# Fabrickit-Bare-Brick.net
KiCad netlist of a schematic drawn in EAGLE
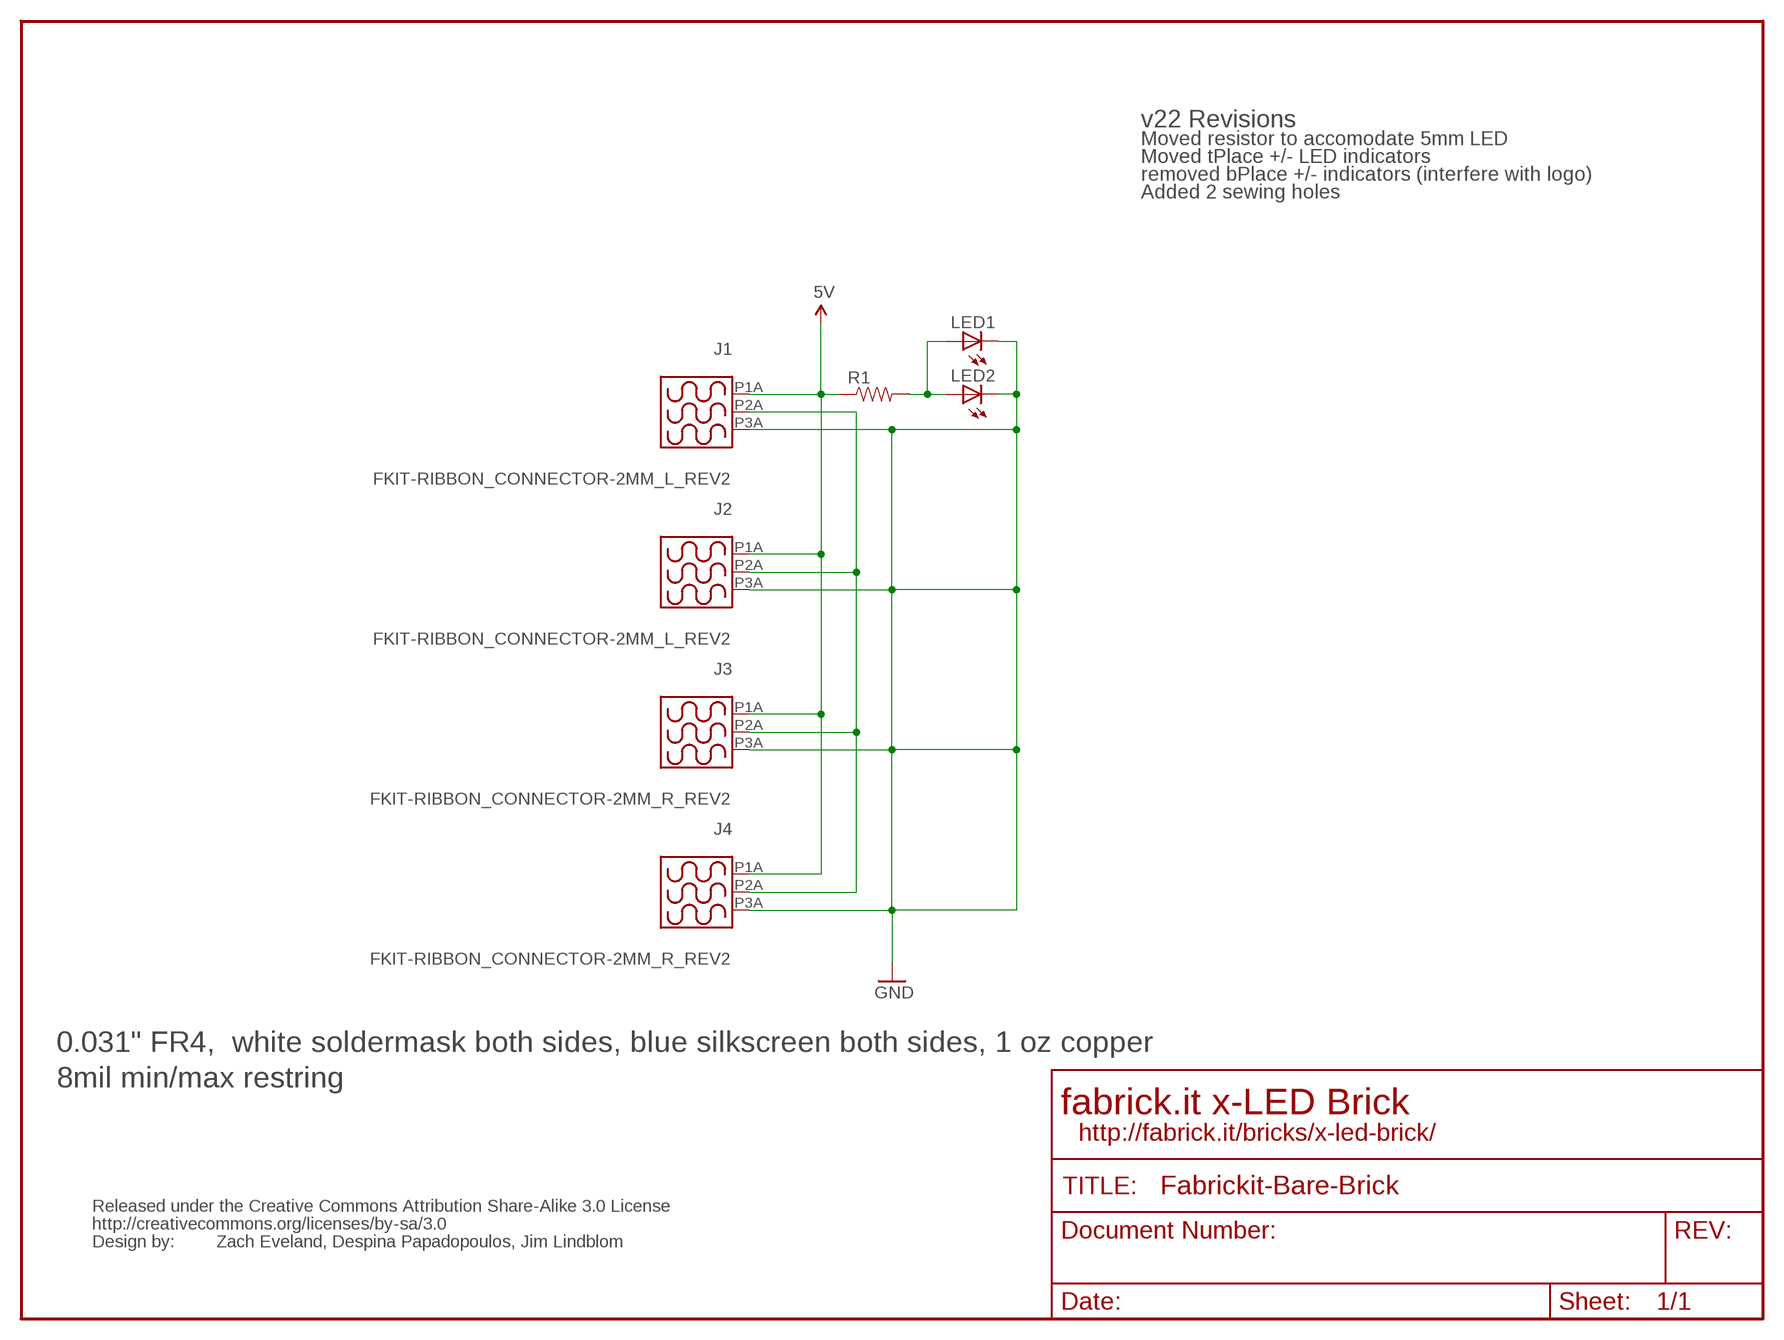
[diagram p0: schematic, sheet 1]

(export (version "E")
  (design (tool "Eeschema 10.0.6"))
  (components
    (comp (ref "J1")
      (value "FKIT-RIBBON_CONNECTOR-2MM_L_REV2")
      (footprint "eagle-import:FKIT-RIBBON_CONNECTOR_03_2MM_L")
      (libsource (lib "eagle-import") (part "FKIT-RIBBON_CONNECTOR-2MM_L_REV2"))
    )
    (comp (ref "J2")
      (value "FKIT-RIBBON_CONNECTOR-2MM_L_REV2")
      (footprint "eagle-import:FKIT-RIBBON_CONNECTOR_03_2MM_L")
      (libsource (lib "eagle-import") (part "FKIT-RIBBON_CONNECTOR-2MM_L_REV2"))
    )
    (comp (ref "J3")
      (value "FKIT-RIBBON_CONNECTOR-2MM_R_REV2")
      (footprint "eagle-import:FKIT-RIBBON_CONNECTOR_03_2MM_R")
      (libsource (lib "eagle-import") (part "FKIT-RIBBON_CONNECTOR-2MM_R_REV2"))
    )
    (comp (ref "J4")
      (value "FKIT-RIBBON_CONNECTOR-2MM_R_REV2")
      (footprint "eagle-import:FKIT-RIBBON_CONNECTOR_03_2MM_R")
      (libsource (lib "eagle-import") (part "FKIT-RIBBON_CONNECTOR-2MM_R_REV2"))
    )
    (comp (ref "LED1")
      (value "LED")
      (footprint "eagle-import:FKIT-LED-1206_NO_CREAM")
      (libsource (lib "eagle-import") (part "LED"))
    )
    (comp (ref "LED2")
      (value "LED-3MM-NO_SILK")
      (footprint "eagle-import:LED3MM-NS")
      (libsource (lib "eagle-import") (part "LED-3MM-NO_SILK"))
    )
    (comp (ref "R1")
      (value "RESISTOR0603")
      (footprint "eagle-import:0603-RES")
      (libsource (lib "eagle-import") (part "RESISTOR0603"))
    )
    (comp (ref "U$1")
      (value "CREATIVE_COMMONS")
      (footprint "eagle-import:CREATIVE_COMMONS")
      (libsource (lib "eagle-import") (part "CREATIVE_COMMONS"))
    )
  )
  (nets
    (net (code "1") (name "5V") (class "Default")
      (node (ref "J1") (pin "P1A") (pinfunction "P$1_P1A") (pintype "bidirectional"))
      (node (ref "J2") (pin "P1A") (pinfunction "P$1_P1A") (pintype "bidirectional"))
      (node (ref "J3") (pin "P1A") (pinfunction "P$1_P1A") (pintype "bidirectional"))
      (node (ref "J4") (pin "P1A") (pinfunction "P$1_P1A") (pintype "bidirectional"))
      (node (ref "R1") (pin "1") (pinfunction "1_1") (pintype "passive"))
    )
    (net (code "2") (name "GND") (class "Default")
      (node (ref "J1") (pin "P3A") (pinfunction "P$3_P3A") (pintype "bidirectional"))
      (node (ref "J2") (pin "P3A") (pinfunction "P$3_P3A") (pintype "bidirectional"))
      (node (ref "J3") (pin "P3A") (pinfunction "P$3_P3A") (pintype "bidirectional"))
      (node (ref "J4") (pin "P3A") (pinfunction "P$3_P3A") (pintype "bidirectional"))
      (node (ref "LED1") (pin "C") (pinfunction "C_C") (pintype "passive"))
      (node (ref "LED2") (pin "K") (pinfunction "C_K") (pintype "passive"))
    )
    (net (code "3") (name "Net-(J1-P$2)") (class "Default")
      (node (ref "J1") (pin "P2A") (pinfunction "P$2_P2A") (pintype "bidirectional"))
      (node (ref "J2") (pin "P2A") (pinfunction "P$2_P2A") (pintype "bidirectional"))
      (node (ref "J3") (pin "P2A") (pinfunction "P$2_P2A") (pintype "bidirectional"))
      (node (ref "J4") (pin "P2A") (pinfunction "P$2_P2A") (pintype "bidirectional"))
    )
    (net (code "4") (name "Net-(LED1-PadA)") (class "Default")
      (node (ref "LED1") (pin "A") (pinfunction "A_A") (pintype "passive"))
      (node (ref "LED2") (pin "A") (pinfunction "A_A") (pintype "passive"))
      (node (ref "R1") (pin "2") (pinfunction "2_2") (pintype "passive"))
    )
  )
)
